# LTEW_Radio_Freq.net
KiCad netlist of a schematic drawn in Altium Designer
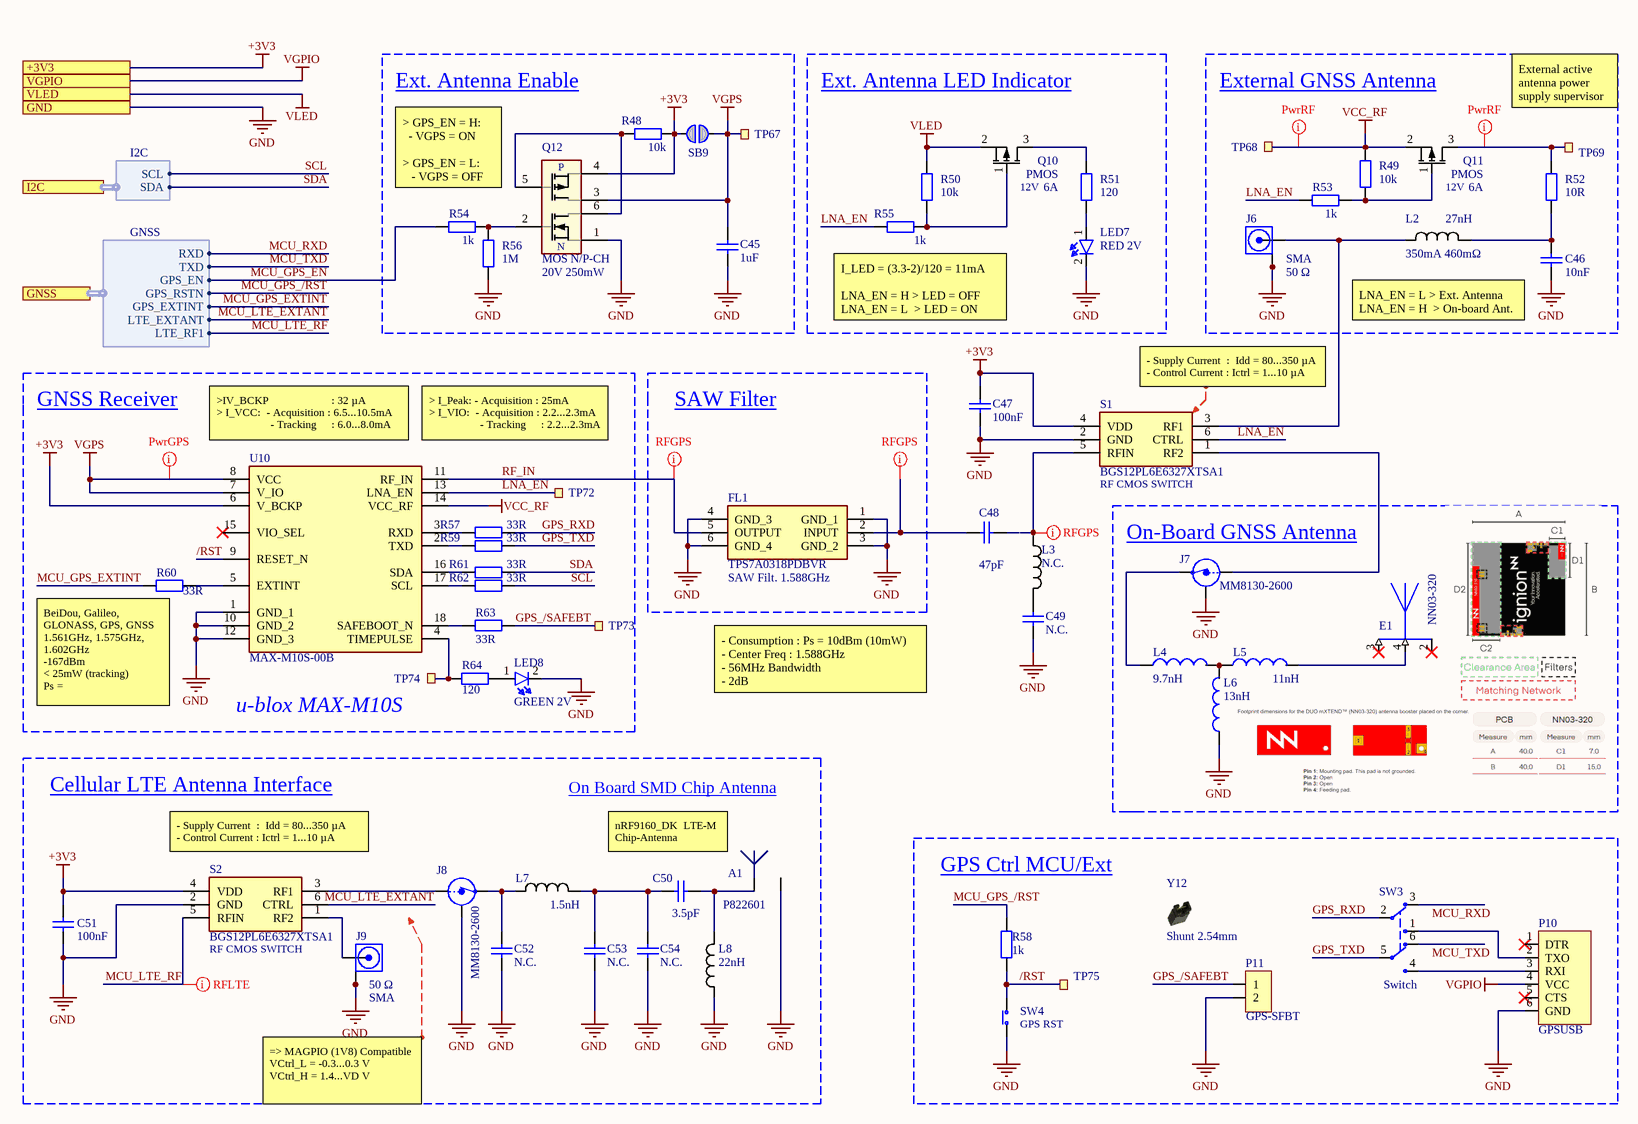
[diagram p0: LTEW_Radio_Freq.SchDoc]

(export (version "E")
  (design (tool "Eeschema 10.0.6"))
  (components
    (comp (ref "A1")
      (value "P822601")
      (footprint "P822601")
      (description "ANTENNA PRESTTA OCTABAND LTE")
      (libsource (lib "LTEWlib") (part "Ant_nRF_9160DK"))
    )
    (comp (ref "C45")
      (value "1uF")
      (footprint "C0603")
      (description "1 µF ±10% 25V Ceramic Capacitor X7R 0603 (1608 Metric)")
      (fields (field (name "MANUFACTURER_PART_NUMBER") "CL10B105KA8NNNC"))
      (libsource (lib "LTEWlib") (part "C_1u"))
    )
    (comp (ref "C46")
      (value "10nF")
      (footprint "C0603")
      (description "10000 pF ±5% 25V Condensateurs céramique C0G, NP0 0603 (1608 métrique)")
      (fields (field (name "MANUFACTURER_PART_NUMBER") "C1608C0G1E103J080AA"))
      (libsource (lib "LTEWlib") (part "C_10n"))
    )
    (comp (ref "C47")
      (value "100nF")
      (footprint "C0603")
      (description "0.1 µF ±10% 25V Ceramic Capacitor X7R 0402 (1005 Metric)")
      (fields (field (name "MANUFACTURER_PART_NUMBER") "CL05B104KA5NNNC"))
      (libsource (lib "LTEWlib") (part "C_100n_0402"))
    )
    (comp (ref "C48")
      (value "47pF")
      (footprint "CAPC1005X55N")
      (description "47 pF ±5% 25V Ceramic Capacitor C0G, NP0 0402 (1005 Metric)")
      (fields (field (name "MANUFACTURER_PART_NUMBER") "0402N470J250CT"))
      (libsource (lib "LTEWlib") (part "C_47p_0402"))
    )
    (comp (ref "C49")
      (value "N.C.")
      (footprint "CAPC1005X55N")
      (description "NC")
      (libsource (lib "LTEWlib") (part "C_NC_0402"))
    )
    (comp (ref "C50")
      (value "3.5pF")
      (footprint "CAPC1005X55N")
      (description "3.5 pF ±0,1pF 50V Condensateurs céramique C0G, NP0 0402 (1005 métrique)")
      (fields (field (name "MANUFACTURER_PART_NUMBER") "GJM1555C1H3R5BB01D"))
      (libsource (lib "LTEWlib") (part "C_0402_3.5p"))
    )
    (comp (ref "C51")
      (value "100nF")
      (footprint "C0603")
      (description "0.1 µF ±10% 25V Condensateurs céramique X7R 0603 (1608 métrique)")
      (fields (field (name "MANUFACTURER_PART_NUMBER") "CL10B104KA8NNNC"))
      (libsource (lib "LTEWlib") (part "C_100n"))
    )
    (comp (ref "C52")
      (value "N.C.")
      (footprint "CAPC1005X55N")
      (description "NC")
      (libsource (lib "LTEWlib") (part "C_NC_0402"))
    )
    (comp (ref "C53")
      (value "N.C.")
      (footprint "CAPC1005X55N")
      (description "NC")
      (libsource (lib "LTEWlib") (part "C_NC_0402"))
    )
    (comp (ref "C54")
      (value "N.C.")
      (footprint "CAPC1005X55N")
      (description "NC")
      (libsource (lib "LTEWlib") (part "C_NC_0402"))
    )
    (comp (ref "E1")
      (value "NN03-320")
      (footprint "LTEWlib:XCVR_NN03-320")
      (libsource (lib "LTEWlib") (part "ANT_GNSS"))
    )
    (comp (ref "FL1")
      (value "TPS7A0318PDBVR")
      (footprint "LTEWlib:B39162B3913U410")
      (description "1.588GHz Frequency GPS RF SAW Filter (Surface Acoustic Wave) 2dB 56MHz Bandwidth 6-SMD, No Lead")
      (fields
        (field (name "MANUFACTURER_PART_NUMBER") "B39162B3913U410")
        (field (name "ALTIUM_VALUE") "SAW Filt. 1.588GHz")
      )
      (libsource (lib "LTEWlib") (part "IC_SAW_FILTER"))
    )
    (comp (ref "J6")
      (value "SMA")
      (footprint "73251-1350 - GNSS")
      (description "SMA Connector Jack, Female Socket 50Ohm Surface Mount Solder")
      (fields (field (name "MANUFACTURER_PART_NUMBER") "73251-1352") (field (name "ALTIUM_VALUE") "50 Ω"))
      (libsource (lib "LTEWlib") (part "CONN_SMA"))
    )
    (comp (ref "J7")
      (value "MM8130-2600")
      (footprint "COAXIAL-SWF - GNSS")
      (description "Coaxial Connector with Switch")
      (fields (field (name "MANUFACTURER") "Murata"))
      (libsource (lib "LTEWlib") (part "MM8130-2600"))
    )
    (comp (ref "J8")
      (value "MM8130-2600")
      (footprint "COAXIAL-SWF - LTE")
      (description "Coaxial Connector with Switch")
      (fields (field (name "MANUFACTURER") "Murata"))
      (libsource (lib "LTEWlib") (part "MM8130-2600"))
    )
    (comp (ref "J9")
      (value "SMA")
      (footprint "73251-1350 - LTE")
      (description "SMA Connector Jack, Female Socket 50Ohm Surface Mount Solder")
      (fields (field (name "MANUFACTURER_PART_NUMBER") "73251-1352") (field (name "ALTIUM_VALUE") "50 Ω"))
      (libsource (lib "") (part "CONN_SMA_1"))
    )
    (comp (ref "L2")
      (value "350mA 460mΩ")
      (footprint "LTEWlib:LQG15WH0N7B02D")
      (description "27 nH Unshielded Multilayer Inductor 350 mA 460mOhm Max 0402 (1005 Metric)")
      (fields (field (name "MANUFACTURER_PART_NUMBER") "LQG15HS27NJ02D") (field (name "ALTIUM_VALUE") "27nH"))
      (libsource (lib "LTEWlib") (part "L_27n"))
    )
    (comp (ref "L3")
      (value "N.C.")
      (footprint "LTEWlib:INDC1005X37N")
      (libsource (lib "LTEWlib") (part "L_0402_NC"))
    )
    (comp (ref "L4")
      (value "9.7nH")
      (footprint "LTEWlib:LQW15AN10NG80D")
      (description "9.7 nH Non blindé Bobiné Inducteur 1.4 A 81mOhms maxi 0402 (1005 métrique)")
      (fields (field (name "MANUFACTURER_PART_NUMBER") "LQW15AN9N7G80D"))
      (libsource (lib "LTEWlib") (part "L_9.7n"))
    )
    (comp (ref "L5")
      (value "11nH")
      (footprint "LTEWlib:LQW15AN10NG80D")
      (description "11 nH Unshielded Drum Core, Wirewound Inductor 1.4 A 65mOhm 0402 (1005 Metric)")
      (fields (field (name "MANUFACTURER_PART_NUMBER") "0402HP-110EGTS"))
      (libsource (lib "LTEWlib") (part "L_11n"))
    )
    (comp (ref "L6")
      (value "13nH")
      (footprint "LTEWlib:LQW15AN10NG80D")
      (description "13 nH Unshielded Drum Core, Wirewound Inductor 870 mA 140mOhm 0402 (1005 Metric)")
      (fields (field (name "MANUFACTURER_PART_NUMBER") "0402HP-130EGTS"))
      (libsource (lib "LTEWlib") (part "L_13n"))
    )
    (comp (ref "L7")
      (value "1.5nH")
      (footprint "LTEWlib:INDC1005X37N")
      (description "1.5 nH Non blindé Couche mince Inducteur 700 mA 250mOhms maxi 0402 (1005 métrique)")
      (fields (field (name "MANUFACTURER_PART_NUMBER") "ATFC-0402-1N5B-T"))
      (libsource (lib "LTEWlib") (part "L_0402_1.5n"))
    )
    (comp (ref "L8")
      (value "22nH")
      (footprint "LTEWlib:LQW15AN10NG80D")
      (description "22 nH Non blindé Bobiné Inducteur 780 mA 202mOhms maxi 0402 (1005 métrique)")
      (fields (field (name "MANUFACTURER_PART_NUMBER") "LQW15AN22NG80D"))
      (libsource (lib "LTEWlib") (part "L_0402_22n"))
    )
    (comp (ref "LED7")
      (value "RED 2V")
      (footprint "LTEWlib:LEDC1608X80N")
      (description "Red 625nm LED Indication - Discrete 2V 0603 (1608 Metric)")
      (fields (field (name "MANUFACTURER_PART_NUMBER") "150060RS75000"))
      (libsource (lib "LTEWlib") (part "LED_R"))
    )
    (comp (ref "LED8")
      (value "GREEN 2V")
      (footprint "LTEWlib:LEDC1608X80N")
      (description "Green 570nm LED Indication - Discrete 2V 0603 (1608 Metric)")
      (fields (field (name "MANUFACTURER_PART_NUMBER") "150060VS75000"))
      (libsource (lib "LTEWlib") (part "LED_G"))
    )
    (comp (ref "P10")
      (value "GPSUSB")
      (footprint "HDR1X6 - GPS")
      (description "Header, 6-Pin")
      (fields
        (field (name "MANUFACTURER_PART_NUMBER") "61300611121")
        (field (name "PUBLISHER") "Altium Limited")
      )
      (libsource (lib "LTEWlib") (part "H_1x6"))
    )
    (comp (ref "P11")
      (value "GPS-SFBT")
      (footprint "HDR1X2 - GPSSAFEBOOT")
      (description "Header, 2-Pin")
      (fields (field (name "MANUFACTURER_PART_NUMBER") "10129378-902001BLF"))
      (libsource (lib "LTEWlib") (part "H_2POS"))
    )
    (comp (ref "Q10")
      (value "PMOS")
      (footprint "LTEWlib:SSM3J332RLFT")
      (description "P-Channel 12 V 6A (Ta) 1W (Ta) Surface Mount SOT-23F")
      (fields
        (field (name "MANUFACTURER_PART_NUMBER") "SSM3J338R")
        (field (name "VALUE2") "6A")
        (field (name "ALTIUM_VALUE") "12V")
      )
      (libsource (lib "LTEWlib") (part "MOS-P"))
    )
    (comp (ref "Q11")
      (value "PMOS")
      (footprint "LTEWlib:SSM3J332RLFT")
      (description "P-Channel 12 V 6A (Ta) 1W (Ta) Surface Mount SOT-23F")
      (fields
        (field (name "MANUFACTURER_PART_NUMBER") "SSM3J338R")
        (field (name "VALUE2") "6A")
        (field (name "ALTIUM_VALUE") "12V")
      )
      (libsource (lib "LTEWlib") (part "MOS-P"))
    )
    (comp (ref "Q12")
      (value "MOS N/P-CH")
      (footprint "LTEWlib:SOT50P160X60-6N")
      (description "Mosfet Array N and P-Channel 20V 485mA, 370mA 250mW Surface Mount SC-89 (SOT-563F)")
      (fields
        (field (name "MANUFACTURER_PART_NUMBER") "SI1016X-T1-GE3")
        (field (name "ALTIUM_VALUE") "20V 250mW")
      )
      (libsource (lib "LTEWlib") (part "MOS_NP_3"))
    )
    (comp (ref "R48")
      (value "10k")
      (footprint "RES0603")
      (description "10 kOhms ±1% 0.1W, 1/10W Chip Resistor 0603 (1608 Metric) Moisture Resistant Thick Film")
      (fields (field (name "MANUFACTURER_PART_NUMBER") "RC0805FR-0710KL"))
      (libsource (lib "") (part "R_10k_1"))
    )
    (comp (ref "R49")
      (value "10k")
      (footprint "RES0603")
      (description "10 kOhms ±1% 0.1W, 1/10W Chip Resistor 0603 (1608 Metric) Moisture Resistant Thick Film")
      (fields (field (name "MANUFACTURER_PART_NUMBER") "RC0805FR-0710KL"))
      (libsource (lib "LTEWlib") (part "R_10k"))
    )
    (comp (ref "R50")
      (value "10k")
      (footprint "RES0603")
      (description "10 kOhms ±1% 0.1W, 1/10W Chip Resistor 0603 (1608 Metric) Moisture Resistant Thick Film")
      (fields (field (name "MANUFACTURER_PART_NUMBER") "RC0805FR-0710KL"))
      (libsource (lib "LTEWlib") (part "R_10k"))
    )
    (comp (ref "R51")
      (value "120")
      (footprint "RES0603")
      (description "1 MOhms ±1% 0.1W, 1/10W Chip Resistor 0603 (1608 Metric) Automotive AEC-Q200 Thick Film")
      (fields (field (name "MANUFACTURER_PART_NUMBER") "CRGCQ0603F120R"))
      (libsource (lib "") (part "R_120_1"))
    )
    (comp (ref "R52")
      (value "10R")
      (footprint "LTEWlib:RESC2012X60N")
      (description "10 Ohms ±5% 0.25W, 1/4W Chip Resistor 0805 (2012 Metric) Automotive AEC-Q200 Thick Film")
      (fields (field (name "MANUFACTURER_PART_NUMBER") "RK73B2ATTD100J"))
      (libsource (lib "LTEWlib") (part "R_10"))
    )
    (comp (ref "R53")
      (value "1k")
      (footprint "RES0603")
      (description "1 kOhms ±1% 0.1W, 1/10W Chip Resistor 0603 (1608 Metric) Moisture Resistant Thick Film")
      (fields (field (name "MANUFACTURER_PART_NUMBER") "RC0603FR-071KL"))
      (libsource (lib "") (part "R_1k_1"))
    )
    (comp (ref "R54")
      (value "1k")
      (footprint "RES0603")
      (description "1 kOhms ±1% 0.1W, 1/10W Chip Resistor 0603 (1608 Metric) Moisture Resistant Thick Film")
      (fields (field (name "MANUFACTURER_PART_NUMBER") "RC0603FR-071KL"))
      (libsource (lib "") (part "R_1k_1"))
    )
    (comp (ref "R55")
      (value "1k")
      (footprint "RES0603")
      (description "1 kOhms ±1% 0.1W, 1/10W Chip Resistor 0603 (1608 Metric) Moisture Resistant Thick Film")
      (fields (field (name "MANUFACTURER_PART_NUMBER") "RC0603FR-071KL"))
      (libsource (lib "") (part "R_1k_1"))
    )
    (comp (ref "R56")
      (value "1M")
      (footprint "RES0603")
      (description "1 MOhms ±1% 0.1W, 1/10W Chip Resistor 0603 (1608 Metric) Automotive AEC-Q200 Thick Film")
      (fields (field (name "MANUFACTURER_PART_NUMBER") "ERJ-3EKF1004V"))
      (libsource (lib "LTEWlib") (part "R_1M"))
    )
    (comp (ref "R57")
      (value "33R")
      (footprint "RES0603")
      (description "33 Ohms ±1% 0.1W, 1/10W Chip Resistor 0603 (1608 Metric) Thin Film")
      (fields (field (name "MANUFACTURER_PART_NUMBER") "RT0603FRE0733RL"))
      (libsource (lib "LTEWlib") (part "R_33"))
    )
    (comp (ref "R58")
      (value "1k")
      (footprint "RES0603")
      (description "1 kOhms ±1% 0.1W, 1/10W Chip Resistor 0603 (1608 Metric) Moisture Resistant Thick Film")
      (fields (field (name "MANUFACTURER_PART_NUMBER") "RC0603FR-071KL"))
      (libsource (lib "LTEWlib") (part "R_1k"))
    )
    (comp (ref "R59")
      (value "33R")
      (footprint "RES0603")
      (description "33 Ohms ±1% 0.1W, 1/10W Chip Resistor 0603 (1608 Metric) Thin Film")
      (fields (field (name "MANUFACTURER_PART_NUMBER") "RT0603FRE0733RL"))
      (libsource (lib "LTEWlib") (part "R_33"))
    )
    (comp (ref "R60")
      (value "33R")
      (footprint "RES0603")
      (description "33 Ohms ±1% 0.1W, 1/10W Chip Resistor 0603 (1608 Metric) Thin Film")
      (fields (field (name "MANUFACTURER_PART_NUMBER") "RT0603FRE0733RL"))
      (libsource (lib "LTEWlib") (part "R_33"))
    )
    (comp (ref "R61")
      (value "33R")
      (footprint "RES0603")
      (description "33 Ohms ±1% 0.1W, 1/10W Chip Resistor 0603 (1608 Metric) Thin Film")
      (fields (field (name "MANUFACTURER_PART_NUMBER") "RT0603FRE0733RL"))
      (libsource (lib "LTEWlib") (part "R_33"))
    )
    (comp (ref "R62")
      (value "33R")
      (footprint "RES0603")
      (description "33 Ohms ±1% 0.1W, 1/10W Chip Resistor 0603 (1608 Metric) Thin Film")
      (fields (field (name "MANUFACTURER_PART_NUMBER") "RT0603FRE0733RL"))
      (libsource (lib "LTEWlib") (part "R_33"))
    )
    (comp (ref "R63")
      (value "33R")
      (footprint "RES0603")
      (description "33 Ohms ±1% 0.1W, 1/10W Chip Resistor 0603 (1608 Metric) Thin Film")
      (fields (field (name "MANUFACTURER_PART_NUMBER") "RT0603FRE0733RL"))
      (libsource (lib "LTEWlib") (part "R_33"))
    )
    (comp (ref "R64")
      (value "120")
      (footprint "RES0603")
      (description "1 MOhms ±1% 0.1W, 1/10W Chip Resistor 0603 (1608 Metric) Automotive AEC-Q200 Thick Film")
      (fields (field (name "MANUFACTURER_PART_NUMBER") "CRGCQ0603F120R"))
      (libsource (lib "LTEWlib") (part "R_120"))
    )
    (comp (ref "S1")
      (value "BGS12PL6E6327XTSA1")
      (footprint "LTEWlib:BGS12WN6E6327XTSA1")
      (description "RF Switch IC WLAN SPDT 50Ohm PG-TSNP-6-10")
      (fields (field (name "ALTIUM_VALUE") "RF CMOS SWITCH"))
      (libsource (lib "LTEWlib") (part "SW_RF_SWITCH"))
    )
    (comp (ref "S2")
      (value "BGS12PL6E6327XTSA1")
      (footprint "LTEWlib:BGS12WN6E6327XTSA1")
      (description "RF Switch IC WLAN SPDT 50Ohm PG-TSNP-6-10")
      (fields (field (name "ALTIUM_VALUE") "RF CMOS SWITCH"))
      (libsource (lib "LTEWlib") (part "SW_RF_SWITCH"))
    )
    (comp (ref "SB9")
      (value "Solderbridge")
      (footprint "Solderbridge")
      (fields (field (name "MANUFACTURER") "N.A."))
      (libsource (lib "pca10090") (part "Solderbridge"))
    )
    (comp (ref "SW3")
      (value "Switch")
      (footprint "JS102011JAQN - GPS")
      (description "SMD slide Switch (ON-ON)")
      (fields (field (name "MANUFACTURER PART NUMBER") "JS202011JAQN"))
      (libsource (lib "LTEWlib") (part "Switch-Slide-RA-J-Lead-DPDT-8.5x3.5mm_C&K"))
    )
    (comp (ref "SW4")
      (value "GPS RST")
      (footprint "Push Button C2.5X3.0 OMRON B3U-1000P(M)-B - GPS RST")
      (description "Tactile Switch, SPNO, SMD, 160gf, 6.2x6.3x2.5mm")
      (fields (field (name "MANUFACTURER_PART_NUMBER") "SKHUALE010"))
      (libsource (lib "LTEWlib") (part "SW_SMD_PB"))
    )
    (comp (ref "TP67")
      (value "Ø1.0mm,SMD")
      (footprint "TP_SMD_Ø0.8mm")
      (description "0.8 mm circular SMD testpad")
      (fields
        (field (name "PART NUMBER") "TP_SMD_Ø1.0MM")
        (field (name "MANUFACTURER") "Nordic Semiconductor")
      )
      (libsource (lib "LTEWlib") (part "TP_SMD"))
    )
    (comp (ref "TP68")
      (value "Ø1.0mm,SMD")
      (footprint "TP_SMD_Ø0.8mm")
      (description "0.8 mm circular SMD testpad")
      (fields
        (field (name "PART NUMBER") "TP_SMD_Ø1.0MM")
        (field (name "MANUFACTURER") "Nordic Semiconductor")
      )
      (libsource (lib "") (part "TP_SMD_1"))
    )
    (comp (ref "TP69")
      (value "Ø1.0mm,SMD")
      (footprint "TP_SMD_Ø0.8mm")
      (description "0.8 mm circular SMD testpad")
      (fields
        (field (name "PART NUMBER") "TP_SMD_Ø1.0MM")
        (field (name "MANUFACTURER") "Nordic Semiconductor")
      )
      (libsource (lib "LTEWlib") (part "TP_SMD"))
    )
    (comp (ref "TP72")
      (value "Ø1.0mm,SMD")
      (footprint "TP_SMD_Ø0.8mm")
      (description "0.8 mm circular SMD testpad")
      (fields
        (field (name "PART NUMBER") "TP_SMD_Ø1.0MM")
        (field (name "MANUFACTURER") "Nordic Semiconductor")
      )
      (libsource (lib "LTEWlib") (part "TP_SMD"))
    )
    (comp (ref "TP73")
      (value "Ø1.0mm,SMD")
      (footprint "TP_SMD_Ø0.8mm")
      (description "0.8 mm circular SMD testpad")
      (fields
        (field (name "PART NUMBER") "TP_SMD_Ø1.0MM")
        (field (name "MANUFACTURER") "Nordic Semiconductor")
      )
      (libsource (lib "LTEWlib") (part "TP_SMD"))
    )
    (comp (ref "TP74")
      (value "Ø1.0mm,SMD")
      (footprint "TP_SMD_Ø0.8mm")
      (description "0.8 mm circular SMD testpad")
      (fields
        (field (name "PART NUMBER") "TP_SMD_Ø1.0MM")
        (field (name "MANUFACTURER") "Nordic Semiconductor")
      )
      (libsource (lib "") (part "TP_SMD_1"))
    )
    (comp (ref "TP75")
      (value "Ø1.0mm,SMD")
      (footprint "TP_SMD_Ø0.8mm")
      (description "0.8 mm circular SMD testpad")
      (fields
        (field (name "PART NUMBER") "TP_SMD_Ø1.0MM")
        (field (name "MANUFACTURER") "Nordic Semiconductor")
      )
      (libsource (lib "LTEWlib") (part "TP_SMD"))
    )
    (comp (ref "U10")
      (value "MAX-M10S-00B")
      (footprint "LTEWlib:MAXM10S00B")
      (libsource (lib "LTEWlib") (part "IC_MAX-M10S"))
    )
    (comp (ref "Y12")
      (value "Shunt 2.54mm")
      (footprint "Shunt_2.54mm_Horizontal")
      (description "Shunt Jumper 2.54mm Black")
      (fields (field (name "MANUFACTURER PART NUMBER") "SPC02SYAN"))
      (libsource (lib "LTEWlib") (part "SHUNT JUMPER 2.54mm BLACK GOLD Horizontal"))
    )
  )
  (nets
    (net (code "3") (name "+3V3") (class "Default")
      (node (ref "C47") (pin "2") (pinfunction "2_2") (pintype "passive"))
      (node (ref "C51") (pin "2") (pinfunction "2_2") (pintype "passive"))
      (node (ref "Q12") (pin "4") (pinfunction "S2_4") (pintype "passive"))
      (node (ref "R48") (pin "1") (pinfunction "1_1") (pintype "passive"))
      (node (ref "S1") (pin "4") (pinfunction "VDD_4") (pintype "passive"))
      (node (ref "S2") (pin "4") (pinfunction "VDD_4") (pintype "passive"))
      (node (ref "SB9") (pin "1") (pinfunction "0_1") (pintype "passive"))
      (node (ref "U10") (pin "6") (pinfunction "V_BCKP_6") (pintype "passive"))
    )
    (net (code "4") (name "/GPS_RXD") (class "Default")
      (node (ref "R57") (pin "2") (pinfunction "2_2") (pintype "passive"))
      (node (ref "SW3") (pin "2") (pinfunction "COM-1_2") (pintype "passive"))
    )
    (net (code "5") (name "/GPS_TXD") (class "Default")
      (node (ref "R59") (pin "2") (pinfunction "2_2") (pintype "passive"))
      (node (ref "SW3") (pin "5") (pinfunction "COM-2_5") (pintype "passive"))
    )
    (net (code "6") (name "/GPS_{slash}SAFEBT") (class "Default")
      (node (ref "P11") (pin "1") (pinfunction "1_1") (pintype "passive"))
      (node (ref "R63") (pin "2") (pinfunction "2_2") (pintype "passive"))
      (node (ref "TP73") (pin "1") (pinfunction "1_1") (pintype "passive"))
    )
    (net (code "7") (name "/LNA_EN") (class "Default")
      (node (ref "R53") (pin "1") (pinfunction "1_1") (pintype "passive"))
      (node (ref "R55") (pin "1") (pinfunction "1_1") (pintype "passive"))
      (node (ref "S1") (pin "6") (pinfunction "CTRL_6") (pintype "passive"))
      (node (ref "TP72") (pin "1") (pinfunction "1_1") (pintype "passive"))
      (node (ref "U10") (pin "13") (pinfunction "LNA_EN_13") (pintype "passive"))
    )
    (net (code "8") (name "/MCU_GPS_EN") (class "Default")
      (node (ref "R54") (pin "1") (pinfunction "1_1") (pintype "passive"))
    )
    (net (code "9") (name "/MCU_GPS_EXTINT") (class "Default")
      (node (ref "R60") (pin "1") (pinfunction "1_1") (pintype "passive"))
    )
    (net (code "10") (name "/MCU_GPS_{slash}RST") (class "Default")
      (node (ref "R58") (pin "2") (pinfunction "2_2") (pintype "passive"))
    )
    (net (code "11") (name "/MCU_LTE_EXTANT") (class "Default")
      (node (ref "S2") (pin "6") (pinfunction "CTRL_6") (pintype "passive"))
    )
    (net (code "12") (name "/MCU_LTE_RF") (class "Default")
      (node (ref "S2") (pin "5") (pinfunction "RFIN_5") (pintype "passive"))
    )
    (net (code "13") (name "/MCU_RXD") (class "Default")
      (node (ref "SW3") (pin "3") (pinfunction "N.C-1_3") (pintype "passive"))
    )
    (net (code "14") (name "/MCU_TXD") (class "Default")
      (node (ref "SW3") (pin "6") (pinfunction "N.C-2_6") (pintype "passive"))
    )
    (net (code "15") (name "/RF_IN") (class "Default")
      (node (ref "FL1") (pin "5") (pinfunction "OUTPUT_5") (pintype "passive"))
      (node (ref "U10") (pin "11") (pinfunction "RF_IN_11") (pintype "passive"))
    )
    (net (code "16") (name "/SCL") (class "Default")
      (node (ref "R62") (pin "2") (pinfunction "2_2") (pintype "passive"))
    )
    (net (code "17") (name "/SDA") (class "Default")
      (node (ref "R61") (pin "2") (pinfunction "2_2") (pintype "passive"))
    )
    (net (code "20") (name "/{slash}RST") (class "Default")
      (node (ref "R58") (pin "1") (pinfunction "1_1") (pintype "passive"))
      (node (ref "SW4") (pin "1") (pinfunction "N.O_1") (pintype "passive"))
      (node (ref "TP75") (pin "1") (pinfunction "1_1") (pintype "passive"))
      (node (ref "U10") (pin "9") (pinfunction "RESET_N_9") (pintype "passive"))
    )
    (net (code "21") (name "GND") (class "Default")
      (node (ref "A1") (pin "2") (pintype "passive"))
      (node (ref "C45") (pin "1") (pinfunction "1_1") (pintype "passive"))
      (node (ref "C46") (pin "1") (pinfunction "1_1") (pintype "passive"))
      (node (ref "C47") (pin "1") (pinfunction "1_1") (pintype "passive"))
      (node (ref "C49") (pin "1") (pinfunction "1_1") (pintype "passive"))
      (node (ref "C51") (pin "1") (pinfunction "1_1") (pintype "passive"))
      (node (ref "C52") (pin "1") (pinfunction "1_1") (pintype "passive"))
      (node (ref "C53") (pin "1") (pinfunction "1_1") (pintype "passive"))
      (node (ref "C54") (pin "1") (pinfunction "1_1") (pintype "passive"))
      (node (ref "FL1") (pin "1") (pinfunction "GND_1_1") (pintype "passive"))
      (node (ref "FL1") (pin "3") (pinfunction "GND_2_3") (pintype "passive"))
      (node (ref "FL1") (pin "4") (pinfunction "GND_3_4") (pintype "passive"))
      (node (ref "FL1") (pin "6") (pinfunction "GND_4_6") (pintype "passive"))
      (node (ref "J6") (pin "1") (pinfunction "1_1") (pintype "passive"))
      (node (ref "J6") (pin "2") (pinfunction "2_2") (pintype "passive"))
      (node (ref "J6") (pin "3") (pinfunction "3_3") (pintype "passive"))
      (node (ref "J6") (pin "4") (pinfunction "4_4") (pintype "passive"))
      (node (ref "J7") (pin "2") (pinfunction "Shield_2") (pintype "passive"))
      (node (ref "J8") (pin "2") (pinfunction "Shield_2") (pintype "passive"))
      (node (ref "J9") (pin "1") (pinfunction "1_1") (pintype "passive"))
      (node (ref "J9") (pin "2") (pinfunction "2_2") (pintype "passive"))
      (node (ref "J9") (pin "3") (pinfunction "3_3") (pintype "passive"))
      (node (ref "J9") (pin "4") (pinfunction "4_4") (pintype "passive"))
      (node (ref "L6") (pin "1") (pinfunction "1_1") (pintype "passive"))
      (node (ref "L8") (pin "2") (pinfunction "2_2") (pintype "passive"))
      (node (ref "LED7") (pin "2") (pinfunction "K_2") (pintype "passive"))
      (node (ref "LED8") (pin "2") (pinfunction "K_2") (pintype "passive"))
      (node (ref "P10") (pin "6") (pinfunction "GND_6") (pintype "passive"))
      (node (ref "P11") (pin "2") (pinfunction "2_2") (pintype "passive"))
      (node (ref "Q12") (pin "1") (pinfunction "S1_1") (pintype "passive"))
      (node (ref "R56") (pin "1") (pinfunction "1_1") (pintype "passive"))
      (node (ref "S1") (pin "2") (pinfunction "GND_2") (pintype "passive"))
      (node (ref "S2") (pin "2") (pinfunction "GND_2") (pintype "passive"))
      (node (ref "SW4") (pin "2") (pinfunction "COM_2") (pintype "passive"))
      (node (ref "U10") (pin "1") (pinfunction "GND_1_1") (pintype "passive"))
      (node (ref "U10") (pin "10") (pinfunction "GND_2_10") (pintype "passive"))
      (node (ref "U10") (pin "12") (pinfunction "GND_3_12") (pintype "passive"))
    )
    (net (code "22") (name "Net-(A1-Pad1)") (class "Default")
      (node (ref "A1") (pin "1") (pintype "passive"))
      (node (ref "C50") (pin "2") (pinfunction "2_2") (pintype "passive"))
      (node (ref "L8") (pin "1") (pinfunction "1_1") (pintype "passive"))
    )
    (net (code "23") (name "Net-(C46-Pad2)") (class "Default")
      (node (ref "C46") (pin "2") (pinfunction "2_2") (pintype "passive"))
      (node (ref "L2") (pin "1") (pinfunction "1_1") (pintype "passive"))
      (node (ref "R52") (pin "1") (pinfunction "1_1") (pintype "passive"))
    )
    (net (code "24") (name "Net-(C49-Pad2)") (class "Default")
      (node (ref "C49") (pin "2") (pinfunction "2_2") (pintype "passive"))
      (node (ref "L3") (pin "2") (pinfunction "2_2") (pintype "passive"))
    )
    (net (code "25") (name "Net-(C50-Pad1)") (class "Default")
      (node (ref "C50") (pin "1") (pinfunction "1_1") (pintype "passive"))
      (node (ref "C53") (pin "2") (pinfunction "2_2") (pintype "passive"))
      (node (ref "C54") (pin "2") (pinfunction "2_2") (pintype "passive"))
      (node (ref "L7") (pin "1") (pinfunction "1_1") (pintype "passive"))
    )
    (net (code "26") (name "Net-(E1-FEED_GNSS)") (class "Default")
      (node (ref "E1") (pin "4") (pinfunction "FEED_GNSS_4") (pintype "input"))
      (node (ref "L5") (pin "2") (pinfunction "2_2") (pintype "passive"))
    )
    (net (code "27") (name "Net-(FL1-INPUT)") (class "Default")
      (node (ref "C48") (pin "1") (pinfunction "1_1") (pintype "passive"))
      (node (ref "FL1") (pin "2") (pinfunction "INPUT_2") (pintype "passive"))
    )
    (net (code "28") (name "Net-(J7-IN)") (class "Default")
      (node (ref "J7") (pin "1") (pinfunction "IN_1") (pintype "passive"))
      (node (ref "S1") (pin "1") (pinfunction "RF2_1") (pintype "passive"))
    )
    (net (code "29") (name "Net-(J7-OUT)") (class "Default")
      (node (ref "J7") (pin "3") (pinfunction "OUT_3") (pintype "passive"))
      (node (ref "L4") (pin "1") (pinfunction "1_1") (pintype "passive"))
    )
    (net (code "30") (name "Net-(J8-IN)") (class "Default")
      (node (ref "J8") (pin "1") (pinfunction "IN_1") (pintype "passive"))
      (node (ref "S2") (pin "3") (pinfunction "RF1_3") (pintype "passive"))
    )
    (net (code "31") (name "Net-(J8-OUT)") (class "Default")
      (node (ref "C52") (pin "2") (pinfunction "2_2") (pintype "passive"))
      (node (ref "J8") (pin "3") (pinfunction "OUT_3") (pintype "passive"))
      (node (ref "L7") (pin "2") (pinfunction "2_2") (pintype "passive"))
    )
    (net (code "32") (name "Net-(L4-Pad2)") (class "Default")
      (node (ref "L4") (pin "2") (pinfunction "2_2") (pintype "passive"))
      (node (ref "L5") (pin "1") (pinfunction "1_1") (pintype "passive"))
      (node (ref "L6") (pin "2") (pinfunction "2_2") (pintype "passive"))
    )
    (net (code "33") (name "Net-(LED7-A)") (class "Default")
      (node (ref "LED7") (pin "1") (pinfunction "A_1") (pintype "passive"))
      (node (ref "R51") (pin "1") (pinfunction "1_1") (pintype "passive"))
    )
    (net (code "34") (name "Net-(LED8-A)") (class "Default")
      (node (ref "LED8") (pin "1") (pinfunction "A_1") (pintype "passive"))
      (node (ref "R64") (pin "1") (pinfunction "1_1") (pintype "passive"))
    )
    (net (code "35") (name "Net-(P10-RXI)") (class "Default")
      (node (ref "P10") (pin "3") (pinfunction "RXI_3") (pintype "passive"))
      (node (ref "SW3") (pin "4") (pinfunction "N.O-2_4") (pintype "passive"))
    )
    (net (code "36") (name "Net-(P10-TXO)") (class "Default")
      (node (ref "P10") (pin "2") (pinfunction "TXO_2") (pintype "passive"))
      (node (ref "SW3") (pin "1") (pinfunction "N.O-1_1") (pintype "passive"))
    )
    (net (code "37") (name "Net-(Q10-D)") (class "Default")
      (node (ref "Q10") (pin "3") (pinfunction "D_3") (pintype "passive"))
      (node (ref "R51") (pin "2") (pinfunction "2_2") (pintype "passive"))
    )
    (net (code "38") (name "Net-(Q10-G)") (class "Default")
      (node (ref "Q10") (pin "1") (pinfunction "G_1") (pintype "passive"))
      (node (ref "R50") (pin "1") (pinfunction "1_1") (pintype "passive"))
      (node (ref "R55") (pin "2") (pinfunction "2_2") (pintype "passive"))
    )
    (net (code "39") (name "Net-(Q11-D)") (class "Default")
      (node (ref "Q11") (pin "3") (pinfunction "D_3") (pintype "passive"))
      (node (ref "R52") (pin "2") (pinfunction "2_2") (pintype "passive"))
      (node (ref "TP69") (pin "1") (pinfunction "1_1") (pintype "passive"))
    )
    (net (code "40") (name "Net-(Q11-G)") (class "Default")
      (node (ref "Q11") (pin "1") (pinfunction "G_1") (pintype "passive"))
      (node (ref "R49") (pin "1") (pinfunction "1_1") (pintype "passive"))
      (node (ref "R53") (pin "2") (pinfunction "2_2") (pintype "passive"))
    )
    (net (code "41") (name "Net-(Q12-D1)") (class "Default")
      (node (ref "Q12") (pin "5") (pinfunction "G2_5") (pintype "passive"))
      (node (ref "Q12") (pin "6") (pinfunction "D1_6") (pintype "passive"))
      (node (ref "R48") (pin "2") (pinfunction "2_2") (pintype "passive"))
    )
    (net (code "42") (name "Net-(Q12-G1)") (class "Default")
      (node (ref "Q12") (pin "2") (pinfunction "G1_2") (pintype "passive"))
      (node (ref "R54") (pin "2") (pinfunction "2_2") (pintype "passive"))
      (node (ref "R56") (pin "2") (pinfunction "2_2") (pintype "passive"))
    )
    (net (code "43") (name "Net-(S1-RF1)") (class "Default")
      (node (ref "J6") (pin "5") (pinfunction "5_5") (pintype "passive"))
      (node (ref "L2") (pin "2") (pinfunction "2_2") (pintype "passive"))
      (node (ref "S1") (pin "3") (pinfunction "RF1_3") (pintype "passive"))
    )
    (net (code "44") (name "Net-(S1-RFIN)") (class "Default")
      (node (ref "C48") (pin "2") (pinfunction "2_2") (pintype "passive"))
      (node (ref "L3") (pin "1") (pinfunction "1_1") (pintype "passive"))
      (node (ref "S1") (pin "5") (pinfunction "RFIN_5") (pintype "passive"))
    )
    (net (code "45") (name "Net-(S2-RF2)") (class "Default")
      (node (ref "J9") (pin "5") (pinfunction "5_5") (pintype "passive"))
      (node (ref "S2") (pin "1") (pinfunction "RF2_1") (pintype "passive"))
    )
    (net (code "46") (name "Net-(U10-EXTINT)") (class "Default")
      (node (ref "R60") (pin "2") (pinfunction "2_2") (pintype "passive"))
      (node (ref "U10") (pin "5") (pinfunction "EXTINT_5") (pintype "passive"))
    )
    (net (code "47") (name "Net-(U10-RXD)") (class "Default")
      (node (ref "R57") (pin "1") (pinfunction "1_1") (pintype "passive"))
      (node (ref "U10") (pin "3") (pinfunction "RXD_3") (pintype "passive"))
    )
    (net (code "48") (name "Net-(U10-SAFEBOOT_N)") (class "Default")
      (node (ref "R63") (pin "1") (pinfunction "1_1") (pintype "passive"))
      (node (ref "U10") (pin "18") (pinfunction "SAFEBOOT_N_18") (pintype "passive"))
    )
    (net (code "49") (name "Net-(U10-SCL)") (class "Default")
      (node (ref "R62") (pin "1") (pinfunction "1_1") (pintype "passive"))
      (node (ref "U10") (pin "17") (pinfunction "SCL_17") (pintype "passive"))
    )
    (net (code "50") (name "Net-(U10-SDA)") (class "Default")
      (node (ref "R61") (pin "1") (pinfunction "1_1") (pintype "passive"))
      (node (ref "U10") (pin "16") (pinfunction "SDA_16") (pintype "passive"))
    )
    (net (code "51") (name "Net-(U10-TIMEPULSE)") (class "Default")
      (node (ref "R64") (pin "2") (pinfunction "2_2") (pintype "passive"))
      (node (ref "TP74") (pin "1") (pinfunction "1_1") (pintype "passive"))
      (node (ref "U10") (pin "4") (pinfunction "TIMEPULSE_4") (pintype "passive"))
    )
    (net (code "52") (name "Net-(U10-TXD)") (class "Default")
      (node (ref "R59") (pin "1") (pinfunction "1_1") (pintype "passive"))
      (node (ref "U10") (pin "2") (pinfunction "TXD_2") (pintype "passive"))
    )
    (net (code "53") (name "VCC_RF") (class "Default")
      (node (ref "Q11") (pin "2") (pinfunction "S_2") (pintype "passive"))
      (node (ref "R49") (pin "2") (pinfunction "2_2") (pintype "passive"))
      (node (ref "TP68") (pin "1") (pinfunction "1_1") (pintype "passive"))
      (node (ref "U10") (pin "14") (pinfunction "VCC_RF_14") (pintype "passive"))
    )
    (net (code "54") (name "VGPIO") (class "Default")
      (node (ref "P10") (pin "4") (pinfunction "VCC_4") (pintype "passive"))
    )
    (net (code "55") (name "VGPS") (class "Default")
      (node (ref "C45") (pin "2") (pinfunction "2_2") (pintype "passive"))
      (node (ref "Q12") (pin "3") (pinfunction "D2_3") (pintype "passive"))
      (node (ref "SB9") (pin "2") (pinfunction "1_2") (pintype "passive"))
      (node (ref "TP67") (pin "1") (pinfunction "1_1") (pintype "passive"))
      (node (ref "U10") (pin "7") (pinfunction "V_IO_7") (pintype "passive"))
      (node (ref "U10") (pin "8") (pinfunction "VCC_8") (pintype "passive"))
    )
    (net (code "56") (name "VLED") (class "Default")
      (node (ref "Q10") (pin "2") (pinfunction "S_2") (pintype "passive"))
      (node (ref "R50") (pin "2") (pinfunction "2_2") (pintype "passive"))
    )
    (net (code "57") (name "unconnected-(E1-FEED_BLUETOOTH-Pad3)") (class "Default")
      (node (ref "E1") (pin "3") (pinfunction "FEED_BLUETOOTH_3") (pintype "input+no_connect"))
    )
    (net (code "58") (name "unconnected-(E1-GROUND-Pad2)") (class "Default")
      (node (ref "E1") (pin "2") (pinfunction "GROUND_2") (pintype "power_in+no_connect"))
    )
    (net (code "59") (name "unconnected-(P10-CTS-Pad5)") (class "Default")
      (node (ref "P10") (pin "5") (pinfunction "CTS_5") (pintype "passive+no_connect"))
    )
    (net (code "60") (name "unconnected-(P10-DTR-Pad1)") (class "Default")
      (node (ref "P10") (pin "1") (pinfunction "DTR_1") (pintype "passive+no_connect"))
    )
    (net (code "61") (name "unconnected-(U10-VIO_SEL-Pad15)") (class "Default")
      (node (ref "U10") (pin "15") (pinfunction "VIO_SEL_15") (pintype "passive+no_connect"))
    )
  )
)
